# e-Tapperhandpiece32.net
KiCad netlist of a schematic drawn in EAGLE
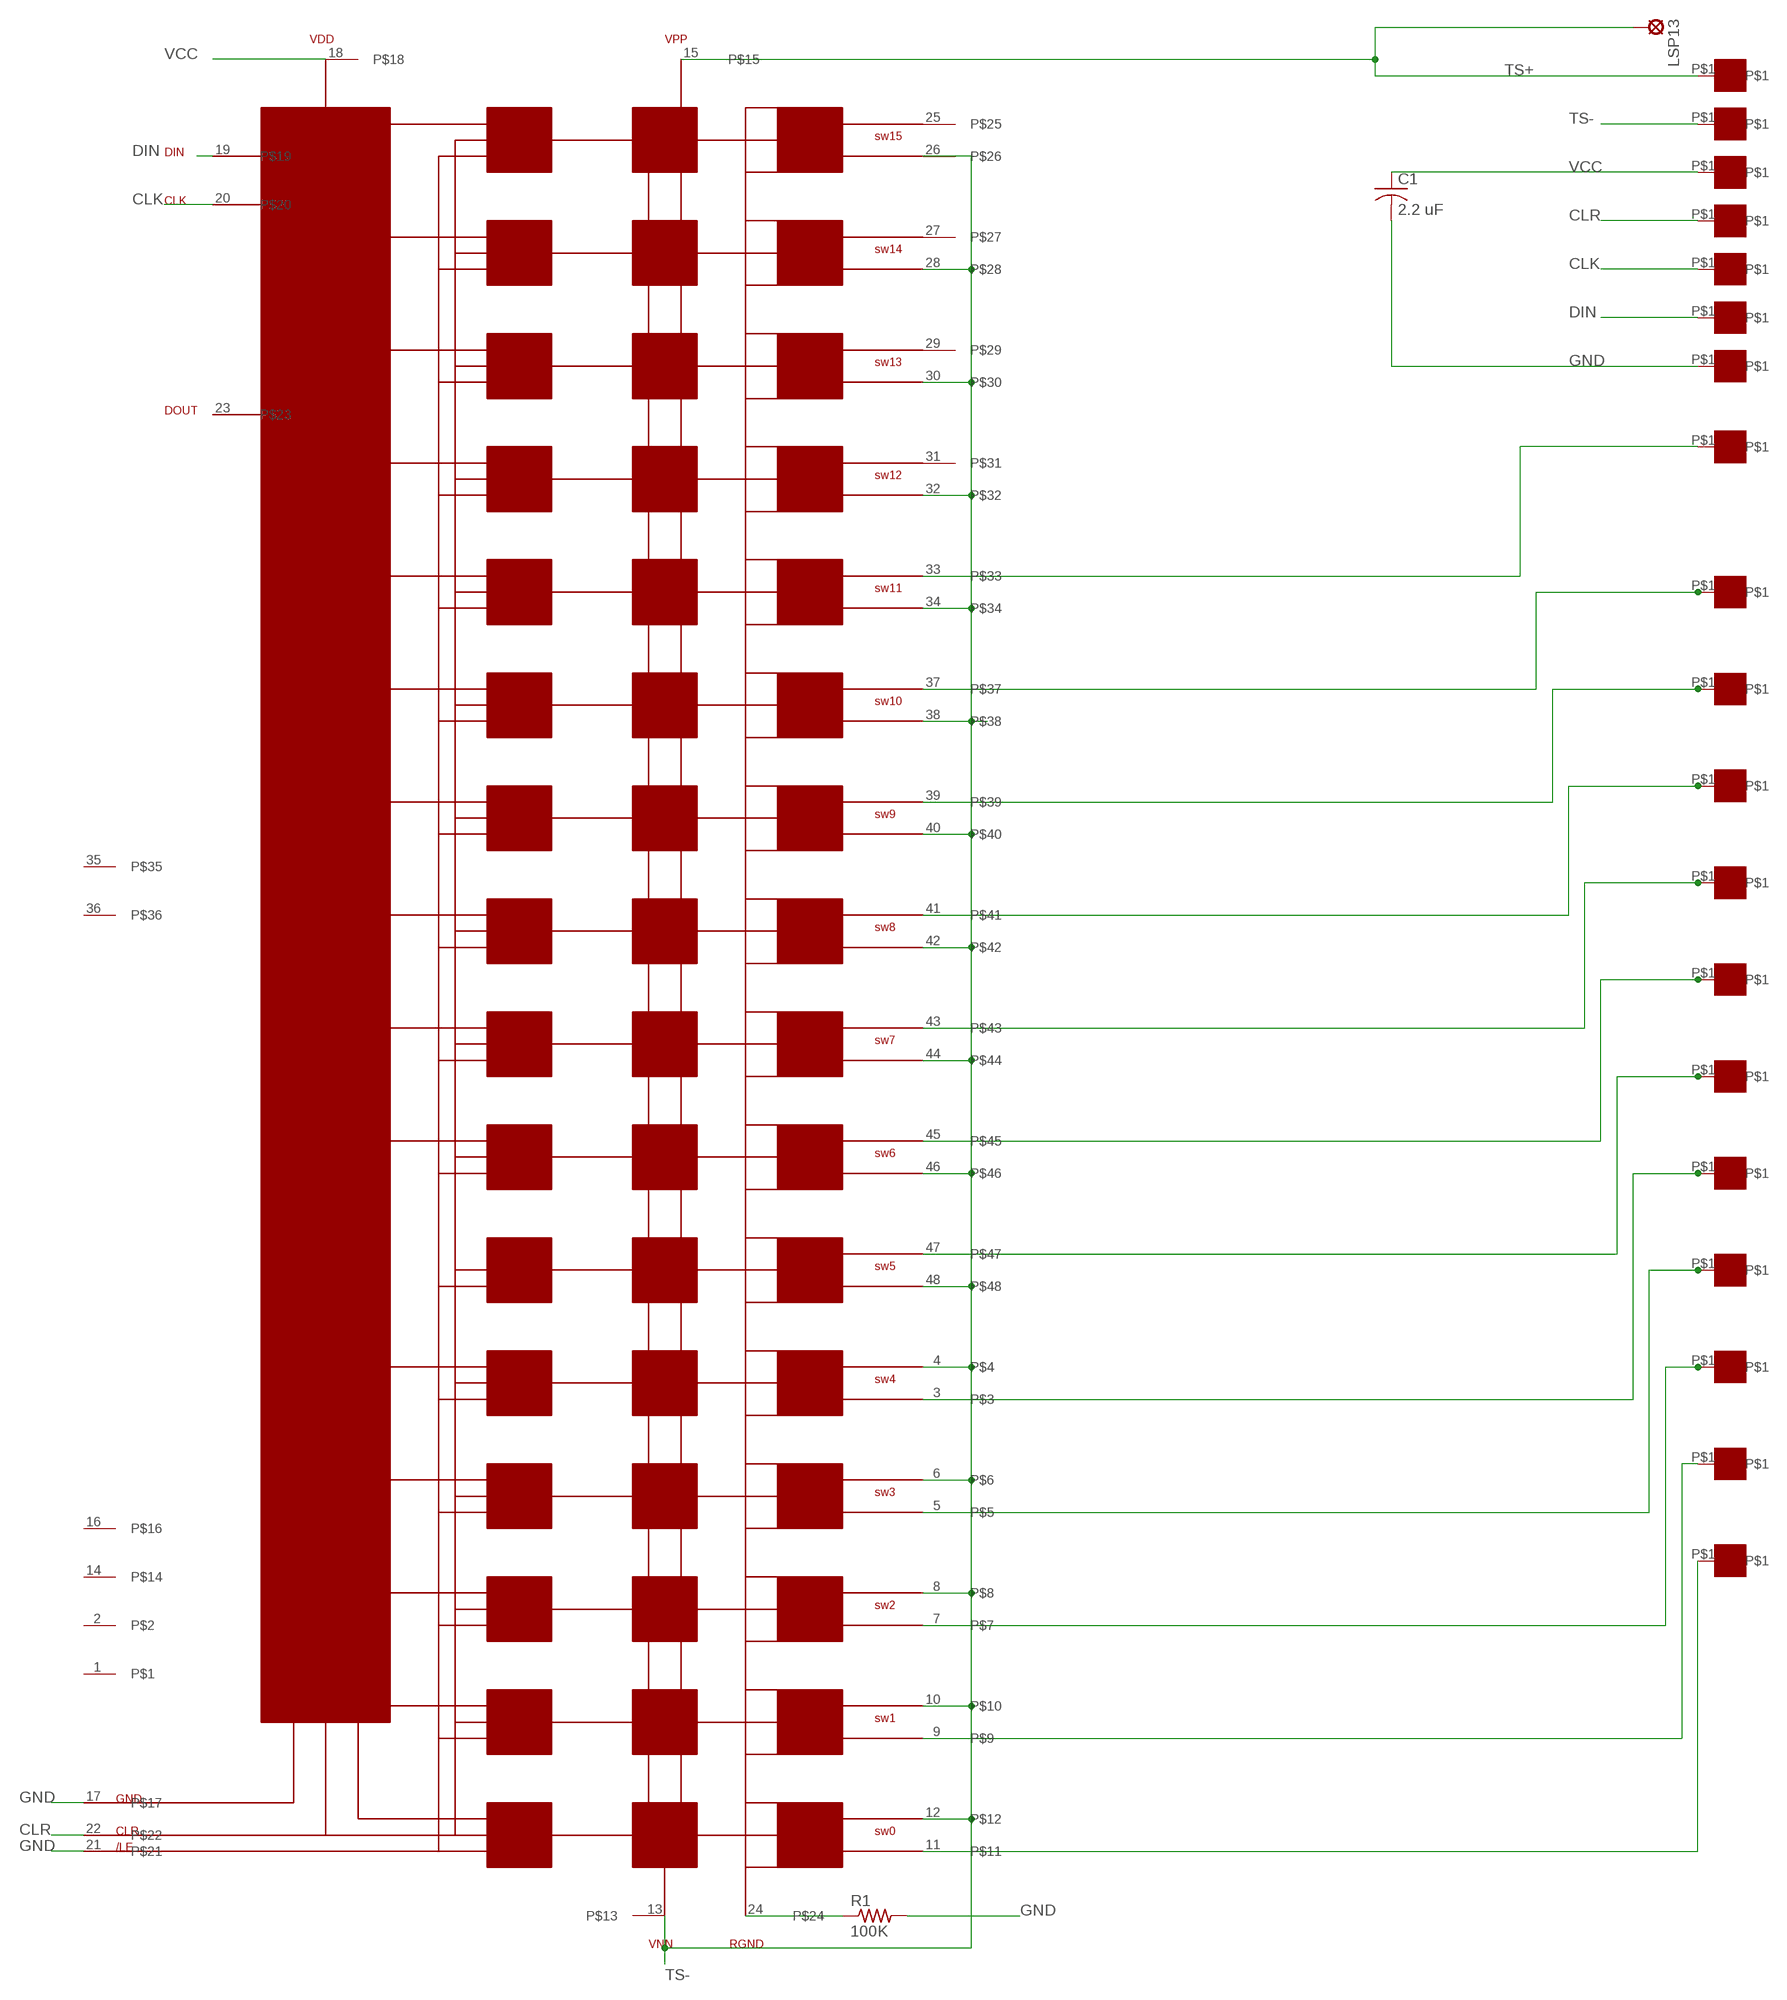
[diagram p0: schematic, sheet 1]

(export (version "E")
  (design (tool "Eeschema 10.0.6"))
  (components
    (comp (ref "C1")
      (value "2.2 uF")
      (footprint "eagle-import:C0805")
      (libsource (lib "eagle-import") (part "C-USC0805"))
    )
    (comp (ref "LSP13")
      (value "SE11")
      (footprint "eagle-import:SE11")
      (libsource (lib "eagle-import") (part "SE11"))
    )
    (comp (ref "R1")
      (value "100K")
      (footprint "eagle-import:R0603")
      (libsource (lib "eagle-import") (part "R-US_R0603"))
    )
    (comp (ref "TSP1")
      (value "ET1")
      (footprint "eagle-import:ET1")
      (libsource (lib "eagle-import") (part "ET1"))
    )
    (comp (ref "TSP2")
      (value "ET1")
      (footprint "eagle-import:ET1")
      (libsource (lib "eagle-import") (part "ET1"))
    )
    (comp (ref "TSP3")
      (value "ET1")
      (footprint "eagle-import:ET1")
      (libsource (lib "eagle-import") (part "ET1"))
    )
    (comp (ref "TSP4")
      (value "ET1")
      (footprint "eagle-import:ET1")
      (libsource (lib "eagle-import") (part "ET1"))
    )
    (comp (ref "TSP5")
      (value "ET1")
      (footprint "eagle-import:ET1")
      (libsource (lib "eagle-import") (part "ET1"))
    )
    (comp (ref "TSP6")
      (value "ET1")
      (footprint "eagle-import:ET1")
      (libsource (lib "eagle-import") (part "ET1"))
    )
    (comp (ref "TSP7")
      (value "ET1")
      (footprint "eagle-import:ET1")
      (libsource (lib "eagle-import") (part "ET1"))
    )
    (comp (ref "TSP8")
      (value "ET1")
      (footprint "eagle-import:ET1")
      (libsource (lib "eagle-import") (part "ET1"))
    )
    (comp (ref "TSP9")
      (value "ET1")
      (footprint "eagle-import:ET1")
      (libsource (lib "eagle-import") (part "ET1"))
    )
    (comp (ref "TSP10")
      (value "ET1")
      (footprint "eagle-import:ET1")
      (libsource (lib "eagle-import") (part "ET1"))
    )
    (comp (ref "TSP11")
      (value "ET1")
      (footprint "eagle-import:ET1")
      (libsource (lib "eagle-import") (part "ET1"))
    )
    (comp (ref "TSP12")
      (value "ET1")
      (footprint "eagle-import:ET1")
      (libsource (lib "eagle-import") (part "ET1"))
    )
    (comp (ref "TSP13")
      (value "ET1")
      (footprint "eagle-import:ET1")
      (libsource (lib "eagle-import") (part "ET1"))
    )
    (comp (ref "TSP14")
      (value "ET1")
      (footprint "eagle-import:ET1")
      (libsource (lib "eagle-import") (part "ET1"))
    )
    (comp (ref "TSP16")
      (value "ET1")
      (footprint "eagle-import:ET1")
      (libsource (lib "eagle-import") (part "ET1"))
    )
    (comp (ref "TSP17")
      (value "ET1")
      (footprint "eagle-import:ET1")
      (libsource (lib "eagle-import") (part "ET1"))
    )
    (comp (ref "TSP18")
      (value "ET1")
      (footprint "eagle-import:ET1")
      (libsource (lib "eagle-import") (part "ET1"))
    )
    (comp (ref "TSP19")
      (value "ET1")
      (footprint "eagle-import:ET1")
      (libsource (lib "eagle-import") (part "ET1"))
    )
    (comp (ref "U1")
      (value "CPC7701")
      (footprint "eagle-import:LQFP48")
      (libsource (lib "eagle-import") (part "CPC7701"))
    )
    (comp (ref "VCC")
      (value "ET1")
      (footprint "eagle-import:ET1")
      (libsource (lib "eagle-import") (part "ET1"))
    )
  )
  (nets
    (net (code "1") (name "/CLK") (class "Default")
      (node (ref "TSP17") (pin "P$1") (pinfunction "P$1_P$1") (pintype "bidirectional"))
      (node (ref "U1") (pin "20") (pinfunction "P$20_20") (pintype "bidirectional"))
    )
    (net (code "2") (name "/CLR") (class "Default")
      (node (ref "TSP18") (pin "P$1") (pinfunction "P$1_P$1") (pintype "bidirectional"))
      (node (ref "U1") (pin "22") (pinfunction "P$22_22") (pintype "bidirectional"))
    )
    (net (code "3") (name "/DIN") (class "Default")
      (node (ref "TSP16") (pin "P$1") (pinfunction "P$1_P$1") (pintype "bidirectional"))
      (node (ref "U1") (pin "19") (pinfunction "P$19_19") (pintype "bidirectional"))
    )
    (net (code "4") (name "/GND") (class "Default")
      (node (ref "C1") (pin "2") (pinfunction "2_2") (pintype "passive"))
      (node (ref "R1") (pin "2") (pinfunction "2_2") (pintype "passive"))
      (node (ref "TSP19") (pin "P$1") (pinfunction "P$1_P$1") (pintype "bidirectional"))
      (node (ref "U1") (pin "17") (pinfunction "P$17_17") (pintype "bidirectional"))
      (node (ref "U1") (pin "21") (pinfunction "P$21_21") (pintype "bidirectional"))
    )
    (net (code "5") (name "/TS+") (class "Default")
      (node (ref "LSP13") (pin "MP") (pinfunction "MP_MP") (pintype "passive"))
      (node (ref "TSP13") (pin "P$1") (pinfunction "P$1_P$1") (pintype "bidirectional"))
      (node (ref "U1") (pin "15") (pinfunction "P$15_15") (pintype "bidirectional"))
    )
    (net (code "6") (name "/TS-") (class "Default")
      (node (ref "TSP14") (pin "P$1") (pinfunction "P$1_P$1") (pintype "bidirectional"))
      (node (ref "U1") (pin "10") (pinfunction "P$10_10") (pintype "bidirectional"))
      (node (ref "U1") (pin "12") (pinfunction "P$12_12") (pintype "bidirectional"))
      (node (ref "U1") (pin "13") (pinfunction "P$13_13") (pintype "bidirectional"))
      (node (ref "U1") (pin "26") (pinfunction "P$26_26") (pintype "bidirectional"))
      (node (ref "U1") (pin "28") (pinfunction "P$28_28") (pintype "bidirectional"))
      (node (ref "U1") (pin "30") (pinfunction "P$30_30") (pintype "bidirectional"))
      (node (ref "U1") (pin "32") (pinfunction "P$32_32") (pintype "bidirectional"))
      (node (ref "U1") (pin "34") (pinfunction "P$34_34") (pintype "bidirectional"))
      (node (ref "U1") (pin "38") (pinfunction "P$38_38") (pintype "bidirectional"))
      (node (ref "U1") (pin "4") (pinfunction "P$4_4") (pintype "bidirectional"))
      (node (ref "U1") (pin "40") (pinfunction "P$40_40") (pintype "bidirectional"))
      (node (ref "U1") (pin "42") (pinfunction "P$42_42") (pintype "bidirectional"))
      (node (ref "U1") (pin "44") (pinfunction "P$44_44") (pintype "bidirectional"))
      (node (ref "U1") (pin "46") (pinfunction "P$46_46") (pintype "bidirectional"))
      (node (ref "U1") (pin "48") (pinfunction "P$48_48") (pintype "bidirectional"))
      (node (ref "U1") (pin "6") (pinfunction "P$6_6") (pintype "bidirectional"))
      (node (ref "U1") (pin "8") (pinfunction "P$8_8") (pintype "bidirectional"))
    )
    (net (code "7") (name "/VCC") (class "Default")
      (node (ref "C1") (pin "1") (pinfunction "1_1") (pintype "passive"))
      (node (ref "U1") (pin "18") (pinfunction "P$18_18") (pintype "bidirectional"))
      (node (ref "VCC") (pin "P$1") (pinfunction "P$1_P$1") (pintype "bidirectional"))
    )
    (net (code "8") (name "Net-(U1-P$3)") (class "Default")
      (node (ref "TSP8") (pin "P$1") (pinfunction "P$1_P$1") (pintype "bidirectional"))
      (node (ref "U1") (pin "3") (pinfunction "P$3_3") (pintype "bidirectional"))
    )
    (net (code "9") (name "Net-(U1-P$5)") (class "Default")
      (node (ref "TSP9") (pin "P$1") (pinfunction "P$1_P$1") (pintype "bidirectional"))
      (node (ref "U1") (pin "5") (pinfunction "P$5_5") (pintype "bidirectional"))
    )
    (net (code "10") (name "Net-(U1-P$7)") (class "Default")
      (node (ref "TSP10") (pin "P$1") (pinfunction "P$1_P$1") (pintype "bidirectional"))
      (node (ref "U1") (pin "7") (pinfunction "P$7_7") (pintype "bidirectional"))
    )
    (net (code "11") (name "Net-(U1-P$9)") (class "Default")
      (node (ref "TSP11") (pin "P$1") (pinfunction "P$1_P$1") (pintype "bidirectional"))
      (node (ref "U1") (pin "9") (pinfunction "P$9_9") (pintype "bidirectional"))
    )
    (net (code "12") (name "Net-(U1-P$11)") (class "Default")
      (node (ref "TSP12") (pin "P$1") (pinfunction "P$1_P$1") (pintype "bidirectional"))
      (node (ref "U1") (pin "11") (pinfunction "P$11_11") (pintype "bidirectional"))
    )
    (net (code "13") (name "Net-(U1-P$24)") (class "Default")
      (node (ref "R1") (pin "1") (pinfunction "1_1") (pintype "passive"))
      (node (ref "U1") (pin "24") (pinfunction "P$24_24") (pintype "bidirectional"))
    )
    (net (code "14") (name "Net-(U1-P$33)") (class "Default")
      (node (ref "TSP1") (pin "P$1") (pinfunction "P$1_P$1") (pintype "bidirectional"))
      (node (ref "U1") (pin "33") (pinfunction "P$33_33") (pintype "bidirectional"))
    )
    (net (code "15") (name "Net-(U1-P$37)") (class "Default")
      (node (ref "TSP2") (pin "P$1") (pinfunction "P$1_P$1") (pintype "bidirectional"))
      (node (ref "U1") (pin "37") (pinfunction "P$37_37") (pintype "bidirectional"))
    )
    (net (code "16") (name "Net-(U1-P$39)") (class "Default")
      (node (ref "TSP3") (pin "P$1") (pinfunction "P$1_P$1") (pintype "bidirectional"))
      (node (ref "U1") (pin "39") (pinfunction "P$39_39") (pintype "bidirectional"))
    )
    (net (code "17") (name "Net-(U1-P$41)") (class "Default")
      (node (ref "TSP4") (pin "P$1") (pinfunction "P$1_P$1") (pintype "bidirectional"))
      (node (ref "U1") (pin "41") (pinfunction "P$41_41") (pintype "bidirectional"))
    )
    (net (code "18") (name "Net-(U1-P$43)") (class "Default")
      (node (ref "TSP5") (pin "P$1") (pinfunction "P$1_P$1") (pintype "bidirectional"))
      (node (ref "U1") (pin "43") (pinfunction "P$43_43") (pintype "bidirectional"))
    )
    (net (code "19") (name "Net-(U1-P$45)") (class "Default")
      (node (ref "TSP6") (pin "P$1") (pinfunction "P$1_P$1") (pintype "bidirectional"))
      (node (ref "U1") (pin "45") (pinfunction "P$45_45") (pintype "bidirectional"))
    )
    (net (code "20") (name "Net-(U1-P$47)") (class "Default")
      (node (ref "TSP7") (pin "P$1") (pinfunction "P$1_P$1") (pintype "bidirectional"))
      (node (ref "U1") (pin "47") (pinfunction "P$47_47") (pintype "bidirectional"))
    )
    (net (code "21") (name "unconnected-(U1-P$1-Pad1)") (class "Default")
      (node (ref "U1") (pin "1") (pinfunction "P$1_1") (pintype "bidirectional"))
    )
    (net (code "22") (name "unconnected-(U1-P$2-Pad2)") (class "Default")
      (node (ref "U1") (pin "2") (pinfunction "P$2_2") (pintype "bidirectional"))
    )
    (net (code "23") (name "unconnected-(U1-P$14-Pad14)") (class "Default")
      (node (ref "U1") (pin "14") (pinfunction "P$14_14") (pintype "bidirectional"))
    )
    (net (code "24") (name "unconnected-(U1-P$16-Pad16)") (class "Default")
      (node (ref "U1") (pin "16") (pinfunction "P$16_16") (pintype "bidirectional"))
    )
    (net (code "25") (name "unconnected-(U1-P$23-Pad23)") (class "Default")
      (node (ref "U1") (pin "23") (pinfunction "P$23_23") (pintype "bidirectional"))
    )
    (net (code "26") (name "unconnected-(U1-P$25-Pad25)") (class "Default")
      (node (ref "U1") (pin "25") (pinfunction "P$25_25") (pintype "bidirectional"))
    )
    (net (code "27") (name "unconnected-(U1-P$27-Pad27)") (class "Default")
      (node (ref "U1") (pin "27") (pinfunction "P$27_27") (pintype "bidirectional"))
    )
    (net (code "28") (name "unconnected-(U1-P$29-Pad29)") (class "Default")
      (node (ref "U1") (pin "29") (pinfunction "P$29_29") (pintype "bidirectional"))
    )
    (net (code "29") (name "unconnected-(U1-P$31-Pad31)") (class "Default")
      (node (ref "U1") (pin "31") (pinfunction "P$31_31") (pintype "bidirectional"))
    )
    (net (code "30") (name "unconnected-(U1-P$35-Pad35)") (class "Default")
      (node (ref "U1") (pin "35") (pinfunction "P$35_35") (pintype "bidirectional"))
    )
    (net (code "31") (name "unconnected-(U1-P$36-Pad36)") (class "Default")
      (node (ref "U1") (pin "36") (pinfunction "P$36_36") (pintype "bidirectional"))
    )
  )
)
